# Sche_Voltage_regulator.net
KiCad netlist of a schematic drawn in Altium Designer
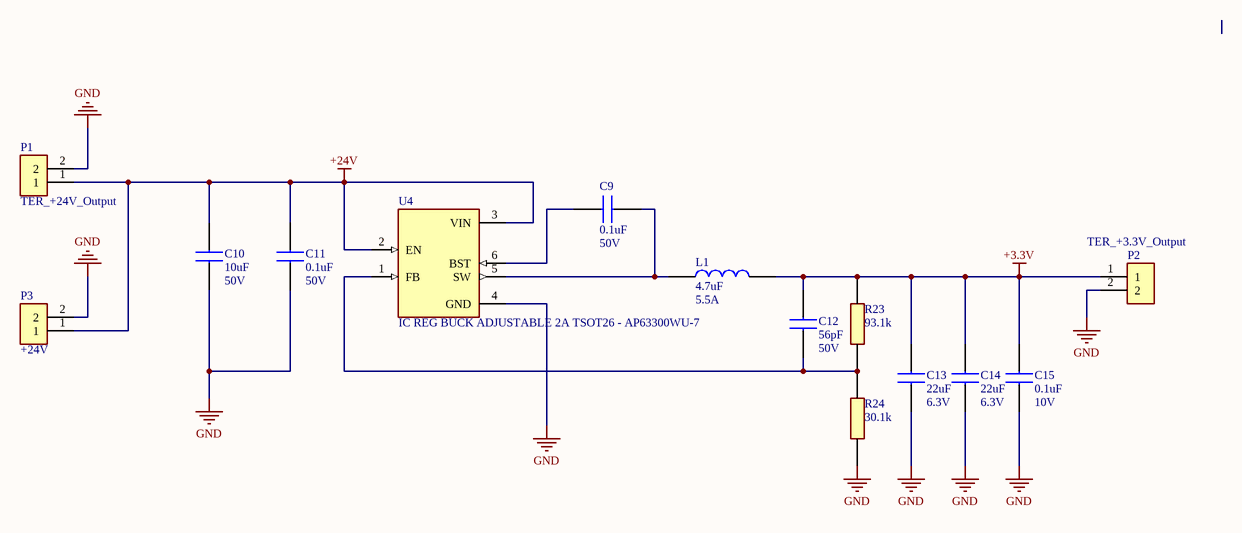
[diagram p0: Sche_Voltage regulator.SchDoc]

(export (version "E")
  (design (tool "Eeschema 10.0.6"))
  (components
    (comp (ref "C9")
      (value "0.1uF")
      (footprint "C 0603")
      (description "CAP CER 0.1UF 50V X7R 0603")
      (fields (field (name "ALTIUM_UNNAMED_1") "50V"))
      (libsource (lib "LAB_COATING COF_MACHINE") (part "CAP CER 0.1UF 50V X7R 0603 - ESD35C104K4T2A-24"))
    )
    (comp (ref "C10")
      (value "10uF")
      (footprint "CAPC3225X290N")
      (description "CAP CER 10UF 50V Y5V 1210")
      (fields
        (field (name "MANUFACTURER_PART_NUMBER") "12105G106ZAT2A/500")
        (field (name "ALTIUM_UNNAMED_1") "50V")
      )
      (libsource (lib "LAB_COATING COF_MACHINE") (part "CAP CER 10UF 50V Y5V 1210 - 12105G106ZAT2A"))
    )
    (comp (ref "C11")
      (value "0.1uF")
      (footprint "C 0603")
      (description "CAP CER 0.1UF 50V X7R 0603")
      (fields (field (name "ALTIUM_UNNAMED_1") "50V"))
      (libsource (lib "LAB_COATING COF_MACHINE") (part "CAP CER 0.1UF 50V X7R 0603 - ESD35C104K4T2A-24"))
    )
    (comp (ref "C12")
      (value "56pF")
      (footprint "CAPC1005X55N")
      (description "CAP CER 56PF 50V C0G/NPO 0402")
      (fields
        (field (name "ALTIUM_UNNAMED_1") "50V")
        (field (name "MANUFACTURER_PART_NUMBER") "CC0402JRNPO9BN560")
      )
      (libsource (lib "LAB_COATING COF_MACHINE") (part "CAP CER 56PF 50V C0G/NPO 0402 - CC0402JRNPO9BN560"))
    )
    (comp (ref "C13")
      (value "22uF")
      (footprint "C 0603")
      (description "CAP CER 22UF 6.3V X5R 0603")
      (fields (field (name "ALTIUM_UNNAMED_1") "6.3V"))
      (libsource (lib "Khang_Library") (part "CAP CER 22UF 6.3V X5R 0603 - GRM188R60J226MEA0D"))
    )
    (comp (ref "C14")
      (value "22uF")
      (footprint "C 0603")
      (description "CAP CER 22UF 6.3V X5R 0603")
      (fields (field (name "ALTIUM_UNNAMED_1") "6.3V"))
      (libsource (lib "Khang_Library") (part "CAP CER 22UF 6.3V X5R 0603 - GRM188R60J226MEA0D"))
    )
    (comp (ref "C15")
      (value "0.1uF")
      (footprint "CAPC1608X95N")
      (description "Multilayer Ceramic Capacitors MLCC - SMD/SMT")
      (fields
        (field (name "ALTIUM_UNNAMED_1") "10V")
        (field (name "MANUFACTURER_PART_NUMBER") "C0603C104K8RACTU/1K")
      )
      (libsource (lib "Khang_Library") (part "CAP CER 0.1UF 10V X7R 0603 - C0603C104K8RACTU"))
    )
    (comp (ref "L1")
      (value "4.7uF")
      (footprint "INDM6965X300N")
      (description "FIXED IND 4.7UH 5.5A 40 MOHM SMD")
      (fields
        (field (name "MANUFACTURER_PART_NUMBER") "IHLP2525CZER4R7M01")
        (field (name "MOUSER PART NUMBER") "70-IHLP2525CZER4R7M1")
        (field (name "ALTIUM_UNNAMED_1") "5.5A")
      )
      (libsource (lib "LAB_COATING COF_MACHINE") (part "IND 4.7UH 5.5A 40 MOHM SMD - IHLP2525CZER4R7M01"))
    )
    (comp (ref "P1")
      (value "TERM BLK 2P SIDE ENT 5.08MM PCB - 282837-2")
      (footprint "TE_282837-2")
      (description "TERM BLK 2P SIDE ENT 5.08MM PCB")
      (fields
        (field (name "MP") "282837-2")
        (field (name "MF") "TE Connectivity")
        (field (name "COMMENT_1") "TER_+24V_Output")
      )
      (libsource (lib "LAB_COATING COF_MACHINE") (part "TERM BLK 2P SIDE ENT 5.08MM PCB - 282837-2"))
    )
    (comp (ref "P2")
      (value "282837-2")
      (footprint "TE_282837-2")
      (description "Connector Terminal Blocks Receptacle 2 Position 5.08mm Solder Straight Thru-Hole 13.5A/Contact")
      (fields (field (name "MF") "TE Connectivity") (field (name "COMMENT_1") "TER_+3.3V_Output"))
      (libsource (lib "") (part "282837-2_1"))
    )
    (comp (ref "P3")
      (value "282837-2")
      (footprint "TE_282837-2")
      (description "Connector Terminal Blocks Receptacle 2 Position 5.08mm Solder Straight Thru-Hole 13.5A/Contact")
      (fields (field (name "MF") "TE Connectivity") (field (name "COMMENT_1") "+24V"))
      (libsource (lib "Con_TerminalBlock_2Pin_5.08mm") (part "282837-2"))
    )
    (comp (ref "R23")
      (value "93.1k")
      (footprint "RESC1005X40N")
      (description "RES 93.1K OHM 1% 1/16W 0402")
      (fields
        (field (name "MANUFACTURER_PART_NUMBER") "RC0402FR-0793K1L")
        (field (name "MOUSER PART NUMBER") "603-RC0402FR-0793K1L")
      )
      (libsource (lib "LAB_COATING COF_MACHINE") (part "RES 93.1K OHM 1% 1/16W 0402 - RC0402FR-0793K1L"))
    )
    (comp (ref "R24")
      (value "30.1k")
      (footprint "ERJ2RKD1004X")
      (description "RES SMD 30.1K OHM 1% 1/10W 0402")
      (fields
        (field (name "MANUFACTURER_PART_NUMBER") "ERJ-2RKF3012X")
        (field (name "MOUSER PART NUMBER") "667-ERJ-2RKF3012X")
      )
      (libsource (lib "LAB_COATING COF_MACHINE") (part "RES SMD 30.1K OHM 1% 1/10W 0402 - ERJ-2RKF3012X"))
    )
    (comp (ref "U4")
      (value "IC REG BUCK ADJUSTABLE 2A TSOT26 - AP63300WU-7")
      (footprint "VOLT_REGULATOR_AP63300WU-7:SOT95P280X100-6N")
      (description "IC REG BUCK ADJUSTABLE 2A TSOT26")
      (fields (field (name "MP") "AP63300WU-7") (field (name "MF") "Diodes Incorporated"))
      (libsource (lib "LAB_COATING COF_MACHINE") (part "IC REG BUCK ADJUSTABLE 2A TSOT26 - AP63300WU-7"))
    )
  )
  (nets
    (net (code "1") (name "+3.3V") (class "Default")
      (node (ref "C12") (pin "2") (pinfunction "2_2") (pintype "passive"))
      (node (ref "C13") (pin "2") (pinfunction "2_2") (pintype "passive"))
      (node (ref "C14") (pin "2") (pinfunction "2_2") (pintype "passive"))
      (node (ref "C15") (pin "2") (pinfunction "2_2") (pintype "passive"))
      (node (ref "L1") (pin "2") (pinfunction "2_2") (pintype "passive"))
      (node (ref "P2") (pin "1") (pinfunction "1_1") (pintype "passive"))
      (node (ref "R23") (pin "2") (pinfunction "2_2") (pintype "passive"))
    )
    (net (code "2") (name "+24V") (class "Default")
      (node (ref "C10") (pin "2") (pinfunction "2_2") (pintype "passive"))
      (node (ref "C11") (pin "2") (pinfunction "2_2") (pintype "passive"))
      (node (ref "P1") (pin "1") (pinfunction "1_1") (pintype "passive"))
      (node (ref "P3") (pin "1") (pinfunction "1_1") (pintype "passive"))
      (node (ref "U4") (pin "2") (pinfunction "EN_2") (pintype "input"))
      (node (ref "U4") (pin "3") (pinfunction "VIN_3") (pintype "power_in"))
    )
    (net (code "3") (name "GND") (class "Default")
      (node (ref "C10") (pin "1") (pinfunction "1_1") (pintype "passive"))
      (node (ref "C11") (pin "1") (pinfunction "1_1") (pintype "passive"))
      (node (ref "C13") (pin "1") (pinfunction "1_1") (pintype "passive"))
      (node (ref "C14") (pin "1") (pinfunction "1_1") (pintype "passive"))
      (node (ref "C15") (pin "1") (pinfunction "1_1") (pintype "passive"))
      (node (ref "P1") (pin "2") (pinfunction "2_2") (pintype "passive"))
      (node (ref "P2") (pin "2") (pinfunction "2_2") (pintype "passive"))
      (node (ref "P3") (pin "2") (pinfunction "2_2") (pintype "passive"))
      (node (ref "R24") (pin "1") (pinfunction "1_1") (pintype "passive"))
      (node (ref "U4") (pin "4") (pinfunction "GND_4") (pintype "power_in"))
    )
    (net (code "4") (name "Net-(U4-BST)") (class "Default")
      (node (ref "C9") (pin "1") (pinfunction "1_1") (pintype "passive"))
      (node (ref "U4") (pin "6") (pinfunction "BST_6") (pintype "input"))
    )
    (net (code "5") (name "Net-(U4-FB)") (class "Default")
      (node (ref "C12") (pin "1") (pinfunction "1_1") (pintype "passive"))
      (node (ref "R23") (pin "1") (pinfunction "1_1") (pintype "passive"))
      (node (ref "R24") (pin "2") (pinfunction "2_2") (pintype "passive"))
      (node (ref "U4") (pin "1") (pinfunction "FB_1") (pintype "input"))
    )
    (net (code "6") (name "Net-(U4-SW)") (class "Default")
      (node (ref "C9") (pin "2") (pinfunction "2_2") (pintype "passive"))
      (node (ref "L1") (pin "1") (pinfunction "1_1") (pintype "passive"))
      (node (ref "U4") (pin "5") (pinfunction "SW_5") (pintype "output"))
    )
  )
)
